# 03_-_CORE_MCU.net
KiCad netlist of a schematic drawn in Altium Designer
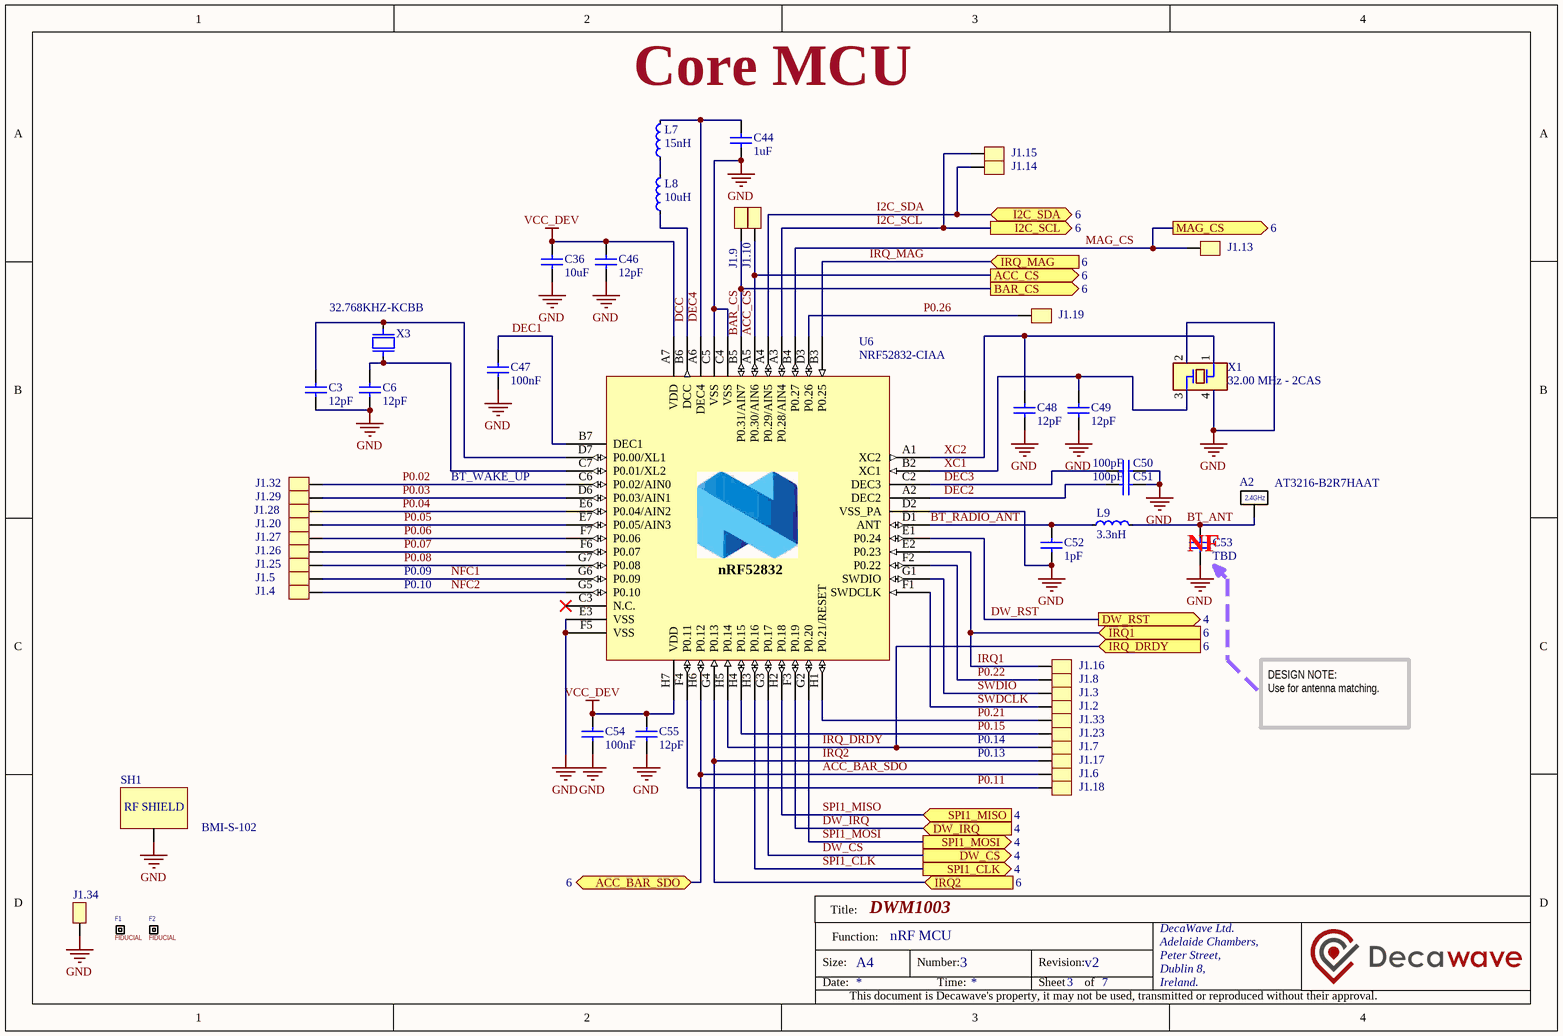
[diagram p0: [03] - CORE MCU.SchDoc]

(export (version "E")
  (design (tool "Eeschema 10.0.6"))
  (components
    (comp (ref "A2")
      (value "AT3216-B2R7HAAT")
      (footprint "AT3216")
      (description "CHIP, 2.45GHZ, 50 OHM, 3.2x1.6 ACX - AAT3216-B2R7HAAT- ANTENNA")
      (fields (field (name "MANUFACTURER") "ACX"))
      (libsource (lib "drak_Library") (part "AT3216-B2R7HAAT"))
    )
    (comp (ref "C3")
      (value "12pF")
      (footprint "C0201")
      (description "CAP CER 12PF 25V NP0 0201")
      (fields
        (field (name "MANUFACTURER") "Murata Electronics North America")
        (field (name "MANUFACTURER PART NUMBER") "GRM0335C1E120JA01D")
      )
      (libsource (lib "drak_Library") (part "GRM0335C1E120JA01D"))
    )
    (comp (ref "C6")
      (value "12pF")
      (footprint "C0201")
      (description "CAP CER 12PF 25V NP0 0201")
      (fields
        (field (name "MANUFACTURER") "Murata Electronics North America")
        (field (name "MANUFACTURER PART NUMBER") "GRM0335C1E120JA01D")
      )
      (libsource (lib "drak_Library") (part "GRM0335C1E120JA01D"))
    )
    (comp (ref "C36")
      (value "10uF")
      (footprint "C0603")
      (description "CAP CER 10UF 6.3V X5R 0603")
      (fields
        (field (name "MANUFACTURER") "Murata Electronics North America")
        (field (name "MANUFACTURER PART NUMBER") "GRM188R60J106ME47D")
      )
      (libsource (lib "drak_Library") (part "GRM188R60J106ME84D"))
    )
    (comp (ref "C44")
      (value "1uF")
      (footprint "C0402")
      (description "CAP CER 1UF 10V X5R 0402")
      (fields
        (field (name "MANUFACTURER") "Murata Electronics North America")
        (field (name "MANUFACTURER PART NUMBER") "GRM155R61A105KE15D")
      )
      (libsource (lib "drak_Library") (part "GRM155R61A105KE15D"))
    )
    (comp (ref "C46")
      (value "12pF")
      (footprint "C0201")
      (description "CAP CER 12PF 25V NP0 0201")
      (fields
        (field (name "MANUFACTURER") "Murata Electronics North America")
        (field (name "MANUFACTURER PART NUMBER") "GRM0335C1E120JA01D")
      )
      (libsource (lib "drak_Library") (part "GRM0335C1E120JA01D"))
    )
    (comp (ref "C47")
      (value "100nF")
      (footprint "C0201")
      (description "CAP CER 0.1UF 25V X6S 0201")
      (fields
        (field (name "MANUFACTURER") "Murata Electronics North America")
        (field (name "MANUFACTURER PART NUMBER") "GRM033C81E104ME14D")
      )
      (libsource (lib "drak_Library") (part "GRM033C81E104ME14D"))
    )
    (comp (ref "C48")
      (value "12pF")
      (footprint "C0201")
      (description "CAP CER 12PF 25V NP0 0201")
      (fields
        (field (name "MANUFACTURER") "Murata Electronics North America")
        (field (name "MANUFACTURER PART NUMBER") "GRM0335C1E120JA01D")
      )
      (libsource (lib "drak_Library") (part "GRM0335C1E120JA01D"))
    )
    (comp (ref "C49")
      (value "12pF")
      (footprint "C0201")
      (description "CAP CER 12PF 25V NP0 0201")
      (fields
        (field (name "MANUFACTURER") "Murata Electronics North America")
        (field (name "MANUFACTURER PART NUMBER") "GRM0335C1E120JA01D")
      )
      (libsource (lib "drak_Library") (part "GRM0335C1E120JA01D"))
    )
    (comp (ref "C50")
      (value "100pF")
      (footprint "C0201")
      (description "CAP CER 100PF 25V NP0 0201")
      (fields
        (field (name "MANUFACTURER") "Murata Electronics North America")
        (field (name "MANUFACTURER PART NUMBER") "GRM0335C1E101JA01D")
      )
      (libsource (lib "drak_Library") (part "GRM0335C1E101JA01D"))
    )
    (comp (ref "C51")
      (value "100pF")
      (footprint "C0201")
      (description "CAP CER 100PF 25V NP0 0201")
      (fields
        (field (name "MANUFACTURER") "Murata Electronics North America")
        (field (name "MANUFACTURER PART NUMBER") "GRM0335C1E101JA01D")
      )
      (libsource (lib "drak_Library") (part "GRM0335C1E101JA01D"))
    )
    (comp (ref "C52")
      (value "1pF")
      (footprint "C0201")
      (description "CAP CER 1PF 50V NP0 0201")
      (fields
        (field (name "MANUFACTURER") "Murata Electronics North America")
        (field (name "MANUFACTURER PART NUMBER") "GRM0335C1H1R0BA01D")
      )
      (libsource (lib "drak_Library") (part "GRM0335C1H1R0BA01D"))
    )
    (comp (ref "C53")
      (value "TBD")
      (footprint "C0201")
      (description "CAP CER 1PF 50V NP0 0201")
      (fields
        (field (name "MANUFACTURER") "Murata Electronics North America")
        (field (name "MANUFACTURER PART NUMBER") "GRM0335C1H1R0BA01D")
      )
      (libsource (lib "drak_Library") (part "GRM0335C1H1R0BA01D"))
    )
    (comp (ref "C54")
      (value "100nF")
      (footprint "C0201")
      (description "CAP CER 0.1UF 25V X6S 0201")
      (fields
        (field (name "MANUFACTURER") "Murata Electronics North America")
        (field (name "MANUFACTURER PART NUMBER") "GRM033C81E104ME14D")
      )
      (libsource (lib "drak_Library") (part "GRM033C81E104ME14D"))
    )
    (comp (ref "C55")
      (value "12pF")
      (footprint "C0201")
      (description "CAP CER 12PF 25V NP0 0201")
      (fields
        (field (name "MANUFACTURER") "Murata Electronics North America")
        (field (name "MANUFACTURER PART NUMBER") "GRM0335C1E120JA01D")
      )
      (libsource (lib "drak_Library") (part "GRM0335C1E120JA01D"))
    )
    (comp (ref "F1")
      (value "FIDUCIAL")
      (footprint "FID1")
      (description "Fiducial 1mm")
      (libsource (lib "drak_Library") (part "FID1"))
    )
    (comp (ref "F2")
      (value "FIDUCIAL")
      (footprint "FID1")
      (description "Fiducial 1mm")
      (libsource (lib "drak_Library") (part "FID1"))
    )
    (comp (ref "J1.2")
      (value "EDGE_PIN")
      (footprint "PCB_EDGE_1MM")
      (description "PCB Edge pin")
      (libsource (lib "") (part "PCB_EDGE_1MM_2"))
    )
    (comp (ref "J1.3")
      (value "EDGE_PIN")
      (footprint "PCB_EDGE_1MM")
      (description "PCB Edge pin")
      (libsource (lib "") (part "PCB_EDGE_1MM_2"))
    )
    (comp (ref "J1.4")
      (value "EDGE_PIN")
      (footprint "PCB_EDGE_1MM")
      (description "PCB Edge pin")
      (libsource (lib "") (part "PCB_EDGE_1MM_3"))
    )
    (comp (ref "J1.5")
      (value "EDGE_PIN")
      (footprint "PCB_EDGE_1MM")
      (description "PCB Edge pin")
      (libsource (lib "") (part "PCB_EDGE_1MM_3"))
    )
    (comp (ref "J1.6")
      (value "EDGE_PIN")
      (footprint "PCB_EDGE_1MM")
      (description "PCB Edge pin")
      (libsource (lib "drak_Library") (part "PCB_EDGE_1MM"))
    )
    (comp (ref "J1.7")
      (value "EDGE_PIN")
      (footprint "PCB_EDGE_1MM")
      (description "PCB Edge pin")
      (libsource (lib "") (part "PCB_EDGE_1MM_2"))
    )
    (comp (ref "J1.8")
      (value "EDGE_PIN")
      (footprint "PCB_EDGE_1MM")
      (description "PCB Edge pin")
      (libsource (lib "") (part "PCB_EDGE_1MM_2"))
    )
    (comp (ref "J1.9")
      (value "EDGE_PIN")
      (footprint "PCB_EDGE_1MM")
      (description "PCB Edge pin")
      (libsource (lib "drak_Library") (part "PCB_EDGE_1MM"))
    )
    (comp (ref "J1.10")
      (value "EDGE_PIN")
      (footprint "PCB_EDGE_1MM")
      (description "PCB Edge pin")
      (libsource (lib "drak_Library") (part "PCB_EDGE_1MM"))
    )
    (comp (ref "J1.13")
      (value "EDGE_PIN")
      (footprint "PCB_EDGE_1MM")
      (description "PCB Edge pin")
      (libsource (lib "") (part "PCB_EDGE_1MM_2"))
    )
    (comp (ref "J1.14")
      (value "EDGE_PIN")
      (footprint "PCB_EDGE_1MM")
      (description "PCB Edge pin")
      (libsource (lib "drak_Library") (part "PCB_EDGE_1MM"))
    )
    (comp (ref "J1.15")
      (value "EDGE_PIN")
      (footprint "PCB_EDGE_1MM")
      (description "PCB Edge pin")
      (libsource (lib "drak_Library") (part "PCB_EDGE_1MM"))
    )
    (comp (ref "J1.16")
      (value "EDGE_PIN")
      (footprint "PCB_EDGE_1MM")
      (description "PCB Edge pin")
      (libsource (lib "") (part "PCB_EDGE_1MM_2"))
    )
    (comp (ref "J1.17")
      (value "EDGE_PIN")
      (footprint "PCB_EDGE_1MM")
      (description "PCB Edge pin")
      (libsource (lib "") (part "PCB_EDGE_1MM_2"))
    )
    (comp (ref "J1.18")
      (value "EDGE_PIN")
      (footprint "PCB_EDGE_1MM")
      (description "PCB Edge pin")
      (libsource (lib "DrakSchlib") (part "EDGE_PIN"))
    )
    (comp (ref "J1.19")
      (value "EDGE_PIN")
      (footprint "PCB_EDGE_1MM")
      (description "PCB Edge pin")
      (libsource (lib "DrakSchlib") (part "EDGE_PIN"))
    )
    (comp (ref "J1.20")
      (value "EDGE_PIN")
      (footprint "PCB_EDGE_1MM")
      (description "PCB Edge pin")
      (libsource (lib "") (part "EDGE_PIN_1"))
    )
    (comp (ref "J1.23")
      (value "EDGE_PIN")
      (footprint "PCB_EDGE_1MM")
      (description "PCB Edge pin")
      (libsource (lib "") (part "PCB_EDGE_1MM_2"))
    )
    (comp (ref "J1.25")
      (value "EDGE_PIN")
      (footprint "PCB_EDGE_1MM")
      (description "PCB Edge pin")
      (libsource (lib "") (part "PCB_EDGE_1MM_3"))
    )
    (comp (ref "J1.26")
      (value "EDGE_PIN")
      (footprint "PCB_EDGE_1MM")
      (description "PCB Edge pin")
      (libsource (lib "") (part "PCB_EDGE_1MM_3"))
    )
    (comp (ref "J1.27")
      (value "EDGE_PIN")
      (footprint "PCB_EDGE_1MM")
      (description "PCB Edge pin")
      (libsource (lib "") (part "PCB_EDGE_1MM_1"))
    )
    (comp (ref "J1.28")
      (value "EDGE_PIN")
      (footprint "PCB_EDGE_1MM")
      (description "PCB Edge pin")
      (libsource (lib "") (part "PCB_EDGE_1MM_1"))
    )
    (comp (ref "J1.29")
      (value "EDGE_PIN")
      (footprint "PCB_EDGE_1MM")
      (description "PCB Edge pin")
      (libsource (lib "") (part "PCB_EDGE_1MM_1"))
    )
    (comp (ref "J1.32")
      (value "EDGE_PIN")
      (footprint "PCB_EDGE_1MM")
      (description "PCB Edge pin")
      (libsource (lib "") (part "PCB_EDGE_1MM_1"))
    )
    (comp (ref "J1.33")
      (value "EDGE_PIN")
      (footprint "PCB_EDGE_1MM")
      (description "PCB Edge pin")
      (libsource (lib "") (part "PCB_EDGE_1MM_2"))
    )
    (comp (ref "J1.34")
      (value "EDGE_PIN")
      (footprint "PCB_EDGE_1MM")
      (description "PCB Edge pin")
      (libsource (lib "drak_Library") (part "PCB_EDGE_1MM"))
    )
    (comp (ref "L7")
      (value "15nH")
      (footprint "INDC1005X05N")
      (description "FIXED IND 15NH 320MA 460 MOHM")
      (fields
        (field (name "MANUFACTURER") "Taiyo Yuden")
        (field (name "MANUFACTURER PART NUMBER") "HK100515NJ-T")
      )
      (libsource (lib "Schlib1") (part "HK100515NJ-T"))
    )
    (comp (ref "L8")
      (value "10uH")
      (footprint "L0603")
      (description "FIXED IND 10UH 80MA 360 MOHM SMD")
      (fields
        (field (name "MANUFACTURER") "Taiyo Yuden")
        (field (name "MANUFACTURER PART NUMBER") "LBMF1608T100K")
      )
      (libsource (lib "drak_Library") (part "LBMF1608T100K"))
    )
    (comp (ref "L9")
      (value "3.3nH")
      (footprint "L0201")
      (description "FIXED IND 3.3NH 400MA 320 MOHM")
      (fields
        (field (name "MANUFACTURER") "Murata Electronics North America")
        (field (name "MANUFACTURER PART NUMBER") "LQP03TG3N3C02D")
      )
      (libsource (lib "drak_Library") (part "LQP03TG3N3C02D"))
    )
    (comp (ref "SH1")
      (value "BMI-S-102")
      (footprint "BMI-S102")
      (description "BOARD SHIELD .65X.65\" 1PIECE")
      (fields (field (name "MANUFACTURER") "Laird Technologies EMI"))
      (libsource (lib "drak_Library") (part "BMI-S-102"))
    )
    (comp (ref "U6")
      (value "NRF52832-CIAA")
      (footprint "BGA50C40P7X8_295X322X50")
      (description "IC RF TXRX+MCU BLUETOOTH 50WLCSP")
      (fields
        (field (name "MANUFACTURER") "Nordic Semiconductor ASA")
        (field (name "MANUFACTURER PART NUMBER") "NRF52832-CIAA-R")
      )
      (libsource (lib "dm1_b2") (part "NRF52832-CIAA-R"))
    )
    (comp (ref "X1")
      (value "32.00 MHz - 2CAS")
      (footprint "ABM10")
      (fields (field (name "MANUFACTURER") "Commutek") (field (name "MANUFACTURER PART NUMBER") "2CAS"))
      (libsource (lib "drak_Library") (part "ABM10"))
    )
    (comp (ref "X3")
      (value "32.768KHZ-KCBB")
      (footprint "PcbLib1:XTAL_SMD_3.2X1.5MM")
      (description "CRYSTAL 32.7680KHZ 12.5PF SMD")
      (fields (field (name "MANUFACTURER") "Commutek") (field (name "MANUFACTURER PART NUMBER") "KCBB"))
      (libsource (lib "drak_Library") (part "ABS06-32.768KHZ-T"))
    )
  )
  (nets
    (net (code "1") (name "/ACC_BAR_SDO") (class "Default")
      (node (ref "J1.6") (pin "0") (pinfunction "0_0") (pintype "passive"))
      (node (ref "U6") (pin "H6") (pinfunction "P0.12_H6") (pintype "bidirectional"))
    )
    (net (code "2") (name "/ACC_CS") (class "Default")
      (node (ref "J1.10") (pin "0") (pinfunction "0_0") (pintype "passive"))
      (node (ref "U6") (pin "A5") (pinfunction "P0.30/AIN6_A5") (pintype "bidirectional"))
    )
    (net (code "3") (name "/BAR_CS") (class "Default")
      (node (ref "J1.9") (pin "0") (pinfunction "0_0") (pintype "passive"))
      (node (ref "U6") (pin "B5") (pinfunction "P0.31/AIN7_B5") (pintype "bidirectional"))
    )
    (net (code "4") (name "/BT_ANT") (class "Default")
      (node (ref "A2") (pin "1") (pintype "passive"))
      (node (ref "C53") (pin "2") (pinfunction "2_2") (pintype "passive"))
      (node (ref "L9") (pin "2") (pinfunction "2_2") (pintype "passive"))
    )
    (net (code "5") (name "/BT_RADIO_ANT") (class "Default")
      (node (ref "C52") (pin "2") (pinfunction "2_2") (pintype "passive"))
      (node (ref "L9") (pin "1") (pinfunction "1_1") (pintype "passive"))
      (node (ref "U6") (pin "D1") (pinfunction "ANT_D1") (pintype "bidirectional"))
    )
    (net (code "6") (name "/DCC") (class "Default")
      (node (ref "L8") (pin "1") (pinfunction "1_1") (pintype "passive"))
      (node (ref "U6") (pin "B6") (pinfunction "DCC_B6") (pintype "output"))
    )
    (net (code "7") (name "/DEC1") (class "Default")
      (node (ref "C47") (pin "2") (pinfunction "2_2") (pintype "passive"))
      (node (ref "U6") (pin "B7") (pinfunction "DEC1_B7") (pintype "power_in"))
    )
    (net (code "8") (name "/DEC2") (class "Default")
      (node (ref "C51") (pin "2") (pinfunction "2_2") (pintype "passive"))
      (node (ref "U6") (pin "A2") (pinfunction "DEC2_A2") (pintype "power_in"))
    )
    (net (code "9") (name "/DEC3") (class "Default")
      (node (ref "C50") (pin "2") (pinfunction "2_2") (pintype "passive"))
      (node (ref "U6") (pin "C2") (pinfunction "DEC3_C2") (pintype "power_in"))
    )
    (net (code "10") (name "/DEC4") (class "Default")
      (node (ref "C44") (pin "2") (pinfunction "2_2") (pintype "passive"))
      (node (ref "L7") (pin "2") (pinfunction "2_2") (pintype "passive"))
      (node (ref "U6") (pin "A6") (pinfunction "DEC4_A6") (pintype "power_in"))
    )
    (net (code "11") (name "/DW_CS") (class "Default")
      (node (ref "U6") (pin "G3") (pinfunction "P0.17_G3") (pintype "bidirectional"))
    )
    (net (code "12") (name "/DW_IRQ") (class "Default")
      (node (ref "U6") (pin "F3") (pinfunction "P0.19_F3") (pintype "bidirectional"))
    )
    (net (code "13") (name "/DW_RST") (class "Default")
      (node (ref "U6") (pin "E1") (pinfunction "P0.24_E1") (pintype "bidirectional"))
    )
    (net (code "14") (name "/I2C_SCL") (class "Default")
      (node (ref "J1.15") (pin "0") (pinfunction "0_0") (pintype "passive"))
      (node (ref "U6") (pin "A3") (pinfunction "P0.28/AIN4_A3") (pintype "bidirectional"))
    )
    (net (code "15") (name "/I2C_SDA") (class "Default")
      (node (ref "J1.14") (pin "0") (pinfunction "0_0") (pintype "passive"))
      (node (ref "U6") (pin "A4") (pinfunction "P0.29/AIN5_A4") (pintype "bidirectional"))
    )
    (net (code "16") (name "/IRQ1") (class "Default")
      (node (ref "J1.16") (pin "0") (pinfunction "0_0") (pintype "passive"))
      (node (ref "U6") (pin "E2") (pinfunction "P0.23_E2") (pintype "input"))
    )
    (net (code "17") (name "/IRQ2") (class "Default")
      (node (ref "J1.17") (pin "0") (pinfunction "0_0") (pintype "passive"))
      (node (ref "U6") (pin "G4") (pinfunction "P0.13_G4") (pintype "input"))
    )
    (net (code "18") (name "/IRQ_DRDY") (class "Default")
      (node (ref "J1.7") (pin "0") (pinfunction "0_0") (pintype "passive"))
      (node (ref "U6") (pin "H5") (pinfunction "P0.14_H5") (pintype "input"))
    )
    (net (code "19") (name "/IRQ_MAG") (class "Default")
      (node (ref "U6") (pin "B3") (pinfunction "P0.25_B3") (pintype "input"))
    )
    (net (code "20") (name "/MAG_CS") (class "Default")
      (node (ref "J1.13") (pin "0") (pinfunction "0_0") (pintype "passive"))
      (node (ref "U6") (pin "B4") (pinfunction "P0.27_B4") (pintype "bidirectional"))
    )
    (net (code "21") (name "/NFC1") (class "Default")
      (node (ref "J1.5") (pin "0") (pinfunction "0_0") (pintype "passive"))
      (node (ref "U6") (pin "G6") (pinfunction "P0.09_G6") (pintype "bidirectional"))
    )
    (net (code "22") (name "/NFC2") (class "Default")
      (node (ref "J1.4") (pin "0") (pinfunction "0_0") (pintype "passive"))
      (node (ref "U6") (pin "G5") (pinfunction "P0.10_G5") (pintype "bidirectional"))
    )
    (net (code "23") (name "/P0.02") (class "Default")
      (node (ref "J1.32") (pin "0") (pinfunction "0_0") (pintype "passive"))
      (node (ref "U6") (pin "C6") (pinfunction "P0.02/AIN0_C6") (pintype "bidirectional"))
    )
    (net (code "24") (name "/P0.03") (class "Default")
      (node (ref "J1.29") (pin "0") (pinfunction "0_0") (pintype "passive"))
      (node (ref "U6") (pin "D6") (pinfunction "P0.03/AIN1_D6") (pintype "bidirectional"))
    )
    (net (code "25") (name "/P0.04") (class "Default")
      (node (ref "J1.28") (pin "0") (pinfunction "0_0") (pintype "passive"))
      (node (ref "U6") (pin "E6") (pinfunction "P0.04/AIN2_E6") (pintype "bidirectional"))
    )
    (net (code "26") (name "/P0.05") (class "Default")
      (node (ref "J1.20") (pin "0") (pinfunction "0_0") (pintype "passive"))
      (node (ref "U6") (pin "E7") (pinfunction "P0.05/AIN3_E7") (pintype "bidirectional"))
    )
    (net (code "27") (name "/P0.06") (class "Default")
      (node (ref "J1.27") (pin "0") (pinfunction "0_0") (pintype "passive"))
      (node (ref "U6") (pin "F7") (pinfunction "P0.06_F7") (pintype "bidirectional"))
    )
    (net (code "28") (name "/P0.07") (class "Default")
      (node (ref "J1.26") (pin "0") (pinfunction "0_0") (pintype "passive"))
      (node (ref "U6") (pin "F6") (pinfunction "P0.07_F6") (pintype "bidirectional"))
    )
    (net (code "29") (name "/P0.08") (class "Default")
      (node (ref "J1.25") (pin "0") (pinfunction "0_0") (pintype "passive"))
      (node (ref "U6") (pin "G7") (pinfunction "P0.08_G7") (pintype "bidirectional"))
    )
    (net (code "30") (name "/P0.11") (class "Default")
      (node (ref "J1.18") (pin "0") (pinfunction "0_0") (pintype "passive"))
      (node (ref "U6") (pin "F4") (pinfunction "P0.11_F4") (pintype "bidirectional"))
    )
    (net (code "31") (name "/P0.15") (class "Default")
      (node (ref "J1.23") (pin "0") (pinfunction "0_0") (pintype "passive"))
      (node (ref "U6") (pin "H4") (pinfunction "P0.15_H4") (pintype "bidirectional"))
    )
    (net (code "32") (name "/P0.21") (class "Default")
      (node (ref "J1.33") (pin "0") (pinfunction "0_0") (pintype "passive"))
      (node (ref "U6") (pin "H1") (pinfunction "P0.21/RESET_H1") (pintype "bidirectional"))
    )
    (net (code "33") (name "/P0.22") (class "Default")
      (node (ref "J1.8") (pin "0") (pinfunction "0_0") (pintype "passive"))
      (node (ref "U6") (pin "F2") (pinfunction "P0.22_F2") (pintype "bidirectional"))
    )
    (net (code "34") (name "/P0.26") (class "Default")
      (node (ref "J1.19") (pin "0") (pinfunction "0_0") (pintype "passive"))
      (node (ref "U6") (pin "D3") (pinfunction "P0.26_D3") (pintype "bidirectional"))
    )
    (net (code "35") (name "/SPI1_CLK") (class "Default")
      (node (ref "U6") (pin "H3") (pinfunction "P0.16_H3") (pintype "bidirectional"))
    )
    (net (code "36") (name "/SPI1_MISO") (class "Default")
      (node (ref "U6") (pin "H2") (pinfunction "P0.18_H2") (pintype "bidirectional"))
    )
    (net (code "37") (name "/SPI1_MOSI") (class "Default")
      (node (ref "U6") (pin "G2") (pinfunction "P0.20_G2") (pintype "bidirectional"))
    )
    (net (code "38") (name "/SWDCLK") (class "Default")
      (node (ref "J1.2") (pin "0") (pinfunction "0_0") (pintype "passive"))
      (node (ref "U6") (pin "F1") (pinfunction "SWDCLK_F1") (pintype "input"))
    )
    (net (code "39") (name "/SWDIO") (class "Default")
      (node (ref "J1.3") (pin "0") (pinfunction "0_0") (pintype "passive"))
      (node (ref "U6") (pin "G1") (pinfunction "SWDIO_G1") (pintype "bidirectional"))
    )
    (net (code "40") (name "/XC1") (class "Default")
      (node (ref "C49") (pin "2") (pinfunction "2_2") (pintype "passive"))
      (node (ref "U6") (pin "B2") (pinfunction "XC1_B2") (pintype "input"))
      (node (ref "X1") (pin "3") (pinfunction "3_3") (pintype "passive"))
    )
    (net (code "41") (name "/XC2") (class "Default")
      (node (ref "C48") (pin "2") (pinfunction "2_2") (pintype "passive"))
      (node (ref "U6") (pin "A1") (pinfunction "XC2_A1") (pintype "output"))
      (node (ref "X1") (pin "1") (pinfunction "1_1") (pintype "passive"))
    )
    (net (code "42") (name "GND") (class "Default")
      (node (ref "C3") (pin "1") (pinfunction "1_1") (pintype "passive"))
      (node (ref "C36") (pin "1") (pinfunction "1_1") (pintype "passive"))
      (node (ref "C44") (pin "1") (pinfunction "1_1") (pintype "passive"))
      (node (ref "C46") (pin "1") (pinfunction "1_1") (pintype "passive"))
      (node (ref "C47") (pin "1") (pinfunction "1_1") (pintype "passive"))
      (node (ref "C48") (pin "1") (pinfunction "1_1") (pintype "passive"))
      (node (ref "C49") (pin "1") (pinfunction "1_1") (pintype "passive"))
      (node (ref "C50") (pin "1") (pinfunction "1_1") (pintype "passive"))
      (node (ref "C51") (pin "1") (pinfunction "1_1") (pintype "passive"))
      (node (ref "C52") (pin "1") (pinfunction "1_1") (pintype "passive"))
      (node (ref "C53") (pin "1") (pinfunction "1_1") (pintype "passive"))
      (node (ref "C54") (pin "1") (pinfunction "1_1") (pintype "passive"))
      (node (ref "C55") (pin "1") (pinfunction "1_1") (pintype "passive"))
      (node (ref "C6") (pin "1") (pinfunction "1_1") (pintype "passive"))
      (node (ref "J1.34") (pin "0") (pinfunction "0_0") (pintype "passive"))
      (node (ref "SH1") (pin "0") (pinfunction "GND_0") (pintype "passive"))
      (node (ref "U6") (pin "C4") (pinfunction "VSS_C4") (pintype "power_in"))
      (node (ref "U6") (pin "C5") (pinfunction "VSS_C5") (pintype "power_in"))
      (node (ref "U6") (pin "D2") (pinfunction "VSS_PA_D2") (pintype "power_in"))
      (node (ref "U6") (pin "E3") (pinfunction "VSS_E3") (pintype "power_in"))
      (node (ref "U6") (pin "F5") (pinfunction "VSS_F5") (pintype "power_in"))
      (node (ref "X1") (pin "2") (pinfunction "2_2") (pintype "passive"))
      (node (ref "X1") (pin "4") (pinfunction "4_4") (pintype "passive"))
    )
    (net (code "43") (name "Net-(L7-Pad1)") (class "Default")
      (node (ref "L7") (pin "1") (pinfunction "1_1") (pintype "passive"))
      (node (ref "L8") (pin "2") (pinfunction "2_2") (pintype "passive"))
    )
    (net (code "44") (name "Net-(U6-P0.00{slash}XL1)") (class "Default")
      (node (ref "C3") (pin "2") (pinfunction "2_2") (pintype "passive"))
      (node (ref "U6") (pin "D7") (pinfunction "P0.00/XL1_D7") (pintype "bidirectional"))
      (node (ref "X3") (pin "2") (pinfunction "2_2") (pintype "passive"))
    )
    (net (code "45") (name "Net-(U6-P0.01{slash}XL2)") (class "Default")
      (node (ref "C6") (pin "2") (pinfunction "2_2") (pintype "passive"))
      (node (ref "U6") (pin "C7") (pinfunction "P0.01/XL2_C7") (pintype "bidirectional"))
      (node (ref "X3") (pin "1") (pinfunction "1_1") (pintype "passive"))
    )
    (net (code "46") (name "VCC_DEV") (class "Default")
      (node (ref "C36") (pin "2") (pinfunction "2_2") (pintype "passive"))
      (node (ref "C46") (pin "2") (pinfunction "2_2") (pintype "passive"))
      (node (ref "C54") (pin "2") (pinfunction "2_2") (pintype "passive"))
      (node (ref "C55") (pin "2") (pinfunction "2_2") (pintype "passive"))
      (node (ref "U6") (pin "A7") (pinfunction "VDD_A7") (pintype "power_in"))
      (node (ref "U6") (pin "H7") (pinfunction "VDD_H7") (pintype "power_in"))
    )
    (net (code "47") (name "unconnected-(U6-N.C.-PadC3)") (class "Default")
      (node (ref "U6") (pin "C3") (pinfunction "N.C._C3") (pintype "power_in+no_connect"))
    )
  )
)
